# cpuConnectionBoard.net
KiCad netlist of a schematic drawn in EAGLE
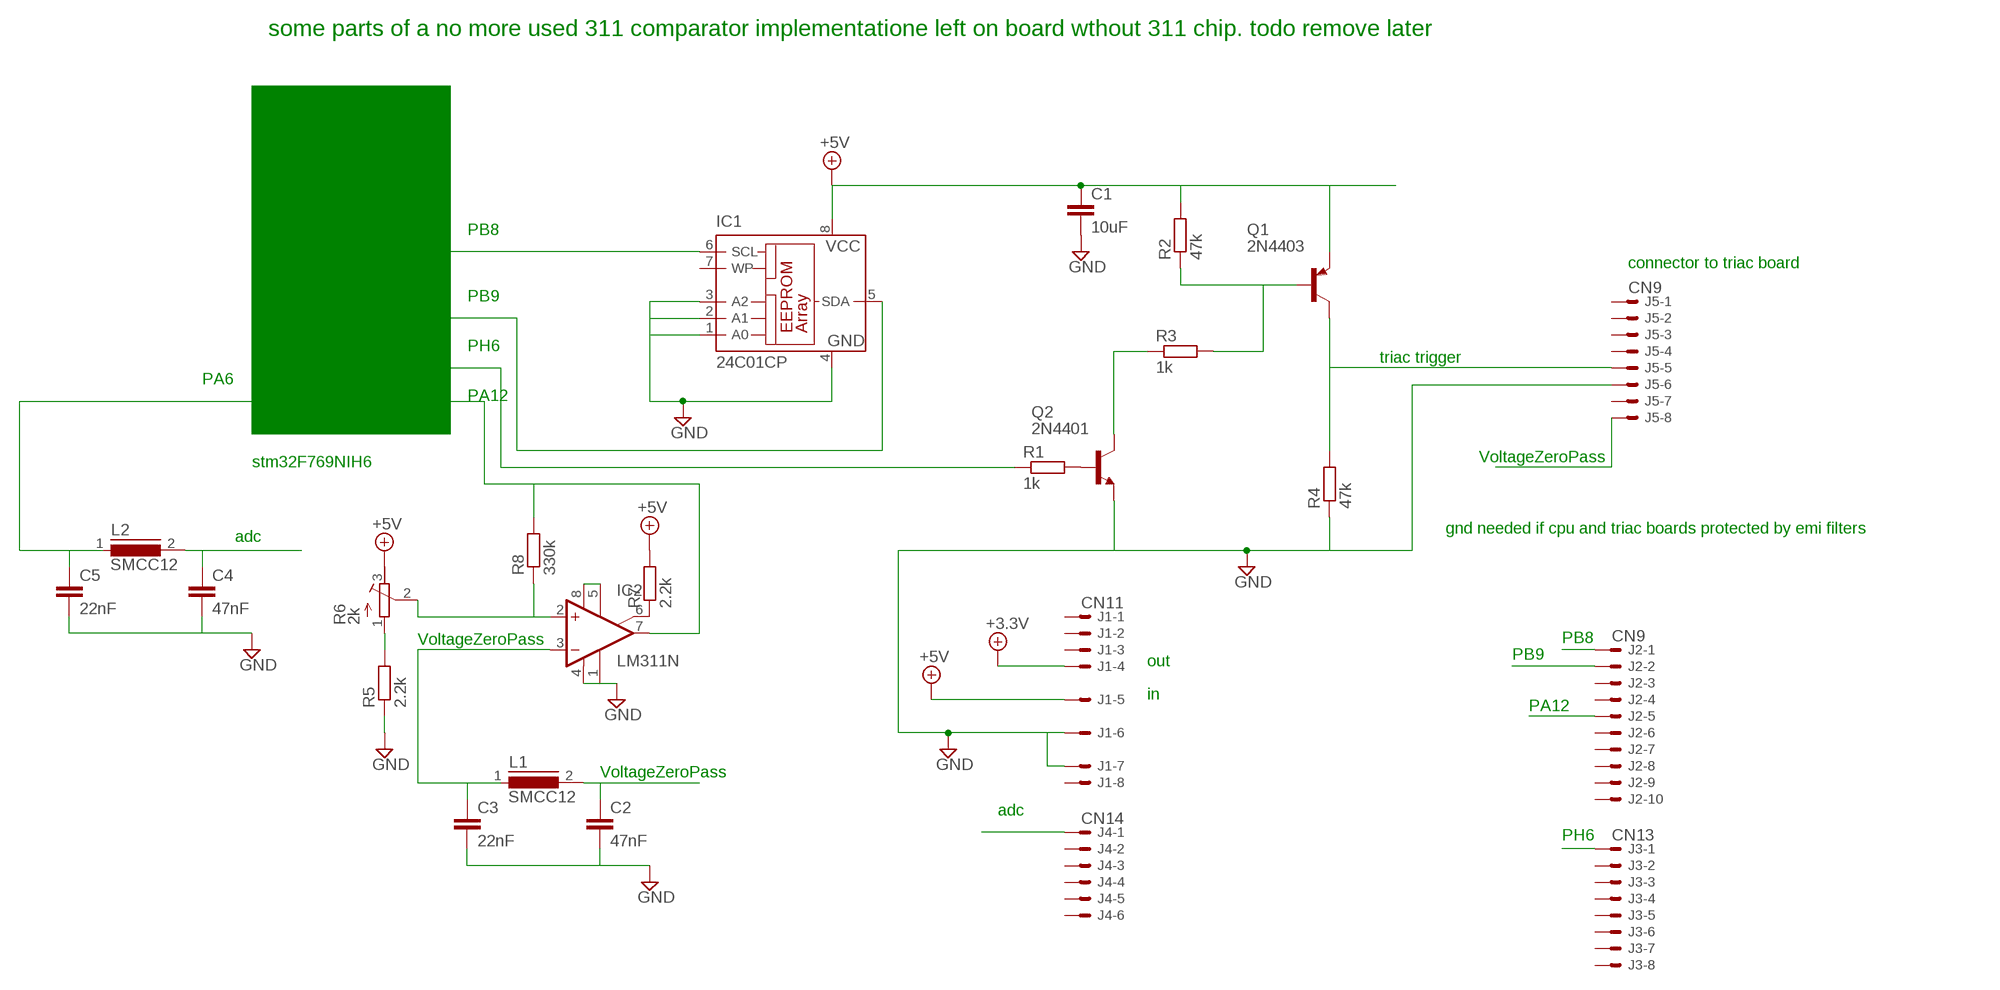
[diagram p0: schematic, sheet 1]

(export (version "E")
  (design (tool "Eeschema 10.0.6"))
  (components
    (comp (ref "C1")
      (value "10uF")
      (footprint "eagle-import:C050-030X075")
      (libsource (lib "eagle-import") (part "C-EU050-030X075"))
    )
    (comp (ref "C2")
      (value "47nF")
      (footprint "eagle-import:C050-030X075")
      (libsource (lib "eagle-import") (part "C-EU050-030X075"))
    )
    (comp (ref "C3")
      (value "22nF")
      (footprint "eagle-import:C050-030X075")
      (libsource (lib "eagle-import") (part "C-EU050-030X075"))
    )
    (comp (ref "C4")
      (value "47nF")
      (footprint "eagle-import:C050-030X075")
      (libsource (lib "eagle-import") (part "C-EU050-030X075"))
    )
    (comp (ref "C5")
      (value "22nF")
      (footprint "eagle-import:C050-030X075")
      (libsource (lib "eagle-import") (part "C-EU050-030X075"))
    )
    (comp (ref "IC1")
      (value "24C01CP")
      (footprint "eagle-import:DIL8")
      (fields (field (name "MF") "MICROCHIP") (field (name "MPN") "24C01C/P"))
      (libsource (lib "eagle-import") (part "24CP01C"))
    )
    (comp (ref "IC2")
      (value "LM311N")
      (footprint "eagle-import:DIL08")
      (libsource (lib "eagle-import") (part "LM311N"))
    )
    (comp (ref "J1")
      (value "CN11")
      (footprint "eagle-import:XF2E-0815-1")
      (fields (field (name "MPN") "XF2E-0815-1"))
      (libsource (lib "eagle-import") (part "XF2-08?15-1E"))
    )
    (comp (ref "J2")
      (value "CN9")
      (footprint "eagle-import:XF2E-1015-1")
      (fields (field (name "MPN") "XF2E-1015-1"))
      (libsource (lib "eagle-import") (part "XF2-10?15-1E"))
    )
    (comp (ref "J3")
      (value "CN13")
      (footprint "eagle-import:XF2E-0815-1")
      (fields (field (name "MPN") "XF2E-0815-1"))
      (libsource (lib "eagle-import") (part "XF2-08?15-1E"))
    )
    (comp (ref "J4")
      (value "CN14")
      (footprint "eagle-import:XF2E-0815-1")
      (fields (field (name "MPN") "XF2E-0815-1"))
      (libsource (lib "eagle-import") (part "XF2-08?15-1E"))
    )
    (comp (ref "J5")
      (value "CN9")
      (footprint "eagle-import:XF2E-1015-1")
      (fields (field (name "MPN") "XF2E-1015-1"))
      (libsource (lib "eagle-import") (part "XF2-10?15-1E"))
    )
    (comp (ref "L1")
      (value "SMCC12")
      (footprint "eagle-import:SMCC12")
      (libsource (lib "eagle-import") (part "SMCC12"))
    )
    (comp (ref "L2")
      (value "SMCC12")
      (footprint "eagle-import:SMCC12")
      (libsource (lib "eagle-import") (part "SMCC12"))
    )
    (comp (ref "Q1")
      (value "2N4403")
      (footprint "eagle-import:TO3")
      (libsource (lib "eagle-import") (part "2N4902"))
    )
    (comp (ref "Q2")
      (value "2N4401")
      (footprint "eagle-import:TO92")
      (libsource (lib "eagle-import") (part "2N4416"))
    )
    (comp (ref "R1")
      (value "1k")
      (footprint "eagle-import:0309_12")
      (libsource (lib "eagle-import") (part "R-EU_0309/12"))
    )
    (comp (ref "R2")
      (value "47k")
      (footprint "eagle-import:0309_12")
      (libsource (lib "eagle-import") (part "R-EU_0309/12"))
    )
    (comp (ref "R3")
      (value "1k")
      (footprint "eagle-import:0309_12")
      (libsource (lib "eagle-import") (part "R-EU_0309/12"))
    )
    (comp (ref "R4")
      (value "47k")
      (footprint "eagle-import:0309_12")
      (libsource (lib "eagle-import") (part "R-EU_0309/12"))
    )
    (comp (ref "R5")
      (value "2.2k")
      (footprint "eagle-import:0309_12")
      (libsource (lib "eagle-import") (part "R-EU_0309/12"))
    )
    (comp (ref "R6")
      (value "2k")
      (footprint "eagle-import:RTRIM64P")
      (libsource (lib "eagle-import") (part "R-TRIMM64P"))
    )
    (comp (ref "R7")
      (value "2.2k")
      (footprint "eagle-import:0309_12")
      (libsource (lib "eagle-import") (part "R-EU_0309/12"))
    )
    (comp (ref "R8")
      (value "330k")
      (footprint "eagle-import:0309_12")
      (libsource (lib "eagle-import") (part "R-EU_0309/12"))
    )
  )
  (nets
    (net (code "1") (name "+3.3V") (class "Default")
      (node (ref "C1") (pin "1") (pinfunction "1_1") (pintype "passive"))
      (node (ref "IC1") (pin "8") (pinfunction "VCC_8") (pintype "power_in"))
      (node (ref "J1") (pin "4") (pinfunction "MS_4") (pintype "passive"))
      (node (ref "J1") (pin "5") (pinfunction "MS_5") (pintype "passive"))
      (node (ref "Q1") (pin "E") (pinfunction "E_E") (pintype "passive"))
      (node (ref "R2") (pin "2") (pinfunction "2_2") (pintype "passive"))
      (node (ref "R6") (pin "3") (pinfunction "E_3") (pintype "passive"))
      (node (ref "R7") (pin "2") (pinfunction "2_2") (pintype "passive"))
    )
    (net (code "2") (name "GND") (class "Default")
      (node (ref "C1") (pin "2") (pinfunction "2_2") (pintype "passive"))
      (node (ref "C2") (pin "2") (pinfunction "2_2") (pintype "passive"))
      (node (ref "C3") (pin "2") (pinfunction "2_2") (pintype "passive"))
      (node (ref "C4") (pin "2") (pinfunction "2_2") (pintype "passive"))
      (node (ref "C5") (pin "2") (pinfunction "2_2") (pintype "passive"))
      (node (ref "IC1") (pin "1") (pinfunction "A0_1") (pintype "input"))
      (node (ref "IC1") (pin "2") (pinfunction "A1_2") (pintype "input"))
      (node (ref "IC1") (pin "3") (pinfunction "A2_3") (pintype "input"))
      (node (ref "IC1") (pin "4") (pinfunction "GND_4") (pintype "power_in"))
      (node (ref "IC2") (pin "4") (pinfunction "V-_4") (pintype "power_in"))
      (node (ref "J1") (pin "6") (pinfunction "MS_6") (pintype "passive"))
      (node (ref "J1") (pin "7") (pinfunction "MS_7") (pintype "passive"))
      (node (ref "J5") (pin "6") (pinfunction "MS_6") (pintype "passive"))
      (node (ref "Q2") (pin "3") (pinfunction "E_3") (pintype "passive"))
      (node (ref "R4") (pin "1") (pinfunction "1_1") (pintype "passive"))
      (node (ref "R5") (pin "1") (pinfunction "1_1") (pintype "passive"))
    )
    (net (code "3") (name "Net-(C2-Pad1)") (class "Default")
      (node (ref "C2") (pin "1") (pinfunction "1_1") (pintype "passive"))
      (node (ref "L1") (pin "2") (pinfunction "2_2") (pintype "passive"))
    )
    (net (code "4") (name "Net-(C4-Pad1)") (class "Default")
      (node (ref "C4") (pin "1") (pinfunction "1_1") (pintype "passive"))
      (node (ref "L2") (pin "2") (pinfunction "2_2") (pintype "passive"))
    )
    (net (code "5") (name "Net-(C5-Pad1)") (class "Default")
      (node (ref "C5") (pin "1") (pinfunction "1_1") (pintype "passive"))
      (node (ref "L2") (pin "1") (pinfunction "1_1") (pintype "passive"))
    )
    (net (code "6") (name "Net-(IC2-+IN)") (class "Default")
      (node (ref "IC2") (pin "2") (pinfunction "+IN_2") (pintype "input"))
      (node (ref "R6") (pin "2") (pinfunction "S_2") (pintype "passive"))
      (node (ref "R8") (pin "1") (pinfunction "1_1") (pintype "passive"))
    )
    (net (code "7") (name "Net-(IC2--IN)") (class "Default")
      (node (ref "C3") (pin "1") (pinfunction "1_1") (pintype "passive"))
      (node (ref "IC2") (pin "3") (pinfunction "-IN_3") (pintype "input"))
    )
    (net (code "8") (name "Net-(IC2-ON)") (class "Default")
      (node (ref "IC2") (pin "5") (pinfunction "ON_5") (pintype "passive"))
      (node (ref "IC2") (pin "8") (pinfunction "V+_8") (pintype "power_in"))
    )
    (net (code "9") (name "Net-(IC2-ON{slash}STR)") (class "Default")
      (node (ref "IC2") (pin "6") (pinfunction "ON/STR_6") (pintype "passive"))
      (node (ref "R7") (pin "1") (pinfunction "1_1") (pintype "passive"))
    )
    (net (code "10") (name "Net-(IC2-OUT)") (class "Default")
      (node (ref "IC2") (pin "7") (pinfunction "OUT_7") (pintype "output"))
      (node (ref "R8") (pin "2") (pinfunction "2_2") (pintype "passive"))
    )
    (net (code "11") (name "Net-(J5F-MS)") (class "Default")
      (node (ref "J5") (pin "5") (pinfunction "MS_5") (pintype "passive"))
      (node (ref "Q1") (pin "C") (pinfunction "C_C") (pintype "passive"))
      (node (ref "Q1") (pin "C/") (pinfunction "C_C/") (pintype "passive"))
      (node (ref "R4") (pin "2") (pinfunction "2_2") (pintype "passive"))
    )
    (net (code "12") (name "Net-(Q1-PadB)") (class "Default")
      (node (ref "Q1") (pin "B") (pinfunction "B_B") (pintype "passive"))
      (node (ref "R2") (pin "1") (pinfunction "1_1") (pintype "passive"))
      (node (ref "R3") (pin "2") (pinfunction "2_2") (pintype "passive"))
    )
    (net (code "13") (name "Net-(Q2-B)") (class "Default")
      (node (ref "Q2") (pin "2") (pinfunction "B_2") (pintype "passive"))
      (node (ref "R1") (pin "2") (pinfunction "2_2") (pintype "passive"))
    )
    (net (code "14") (name "Net-(Q2-C)") (class "Default")
      (node (ref "Q2") (pin "1") (pinfunction "C_1") (pintype "passive"))
      (node (ref "R3") (pin "1") (pinfunction "1_1") (pintype "passive"))
    )
    (net (code "15") (name "Net-(R6-A)") (class "Default")
      (node (ref "R5") (pin "2") (pinfunction "2_2") (pintype "passive"))
      (node (ref "R6") (pin "1") (pinfunction "A_1") (pintype "passive"))
    )
    (net (code "16") (name "unconnected-(IC1-SCL-Pad6)") (class "Default")
      (node (ref "IC1") (pin "6") (pinfunction "SCL_6") (pintype "input"))
    )
    (net (code "17") (name "unconnected-(IC1-SDA-Pad5)") (class "Default")
      (node (ref "IC1") (pin "5") (pinfunction "SDA_5") (pintype "bidirectional"))
    )
    (net (code "18") (name "unconnected-(IC1-WP-Pad7)") (class "Default")
      (node (ref "IC1") (pin "7") (pinfunction "WP_7") (pintype "input"))
    )
    (net (code "19") (name "unconnected-(IC2-GND-Pad1)") (class "Default")
      (node (ref "IC2") (pin "1") (pinfunction "GND_1") (pintype "passive"))
    )
    (net (code "20") (name "unconnected-(J1A-MSV-Pad1)") (class "Default")
      (node (ref "J1") (pin "1") (pinfunction "MSV_1") (pintype "passive"))
    )
    (net (code "21") (name "unconnected-(J1B-MS-Pad2)") (class "Default")
      (node (ref "J1") (pin "2") (pinfunction "MS_2") (pintype "passive"))
    )
    (net (code "22") (name "unconnected-(J1C-MS-Pad3)") (class "Default")
      (node (ref "J1") (pin "3") (pinfunction "MS_3") (pintype "passive"))
    )
    (net (code "23") (name "unconnected-(J1H-MS-Pad8)") (class "Default")
      (node (ref "J1") (pin "8") (pinfunction "MS_8") (pintype "passive"))
    )
    (net (code "24") (name "unconnected-(J2A-MSV-Pad1)") (class "Default")
      (node (ref "J2") (pin "1") (pinfunction "MSV_1") (pintype "passive"))
    )
    (net (code "25") (name "unconnected-(J2B-MS-Pad10)") (class "Default")
      (node (ref "J2") (pin "10") (pinfunction "MS_10") (pintype "passive"))
    )
    (net (code "26") (name "unconnected-(J2C-MS-Pad2)") (class "Default")
      (node (ref "J2") (pin "2") (pinfunction "MS_2") (pintype "passive"))
    )
    (net (code "27") (name "unconnected-(J2D-MS-Pad3)") (class "Default")
      (node (ref "J2") (pin "3") (pinfunction "MS_3") (pintype "passive"))
    )
    (net (code "28") (name "unconnected-(J2E-MS-Pad4)") (class "Default")
      (node (ref "J2") (pin "4") (pinfunction "MS_4") (pintype "passive"))
    )
    (net (code "29") (name "unconnected-(J2F-MS-Pad5)") (class "Default")
      (node (ref "J2") (pin "5") (pinfunction "MS_5") (pintype "passive"))
    )
    (net (code "30") (name "unconnected-(J2G-MS-Pad6)") (class "Default")
      (node (ref "J2") (pin "6") (pinfunction "MS_6") (pintype "passive"))
    )
    (net (code "31") (name "unconnected-(J2H-MS-Pad7)") (class "Default")
      (node (ref "J2") (pin "7") (pinfunction "MS_7") (pintype "passive"))
    )
    (net (code "32") (name "unconnected-(J2I-MS-Pad8)") (class "Default")
      (node (ref "J2") (pin "8") (pinfunction "MS_8") (pintype "passive"))
    )
    (net (code "33") (name "unconnected-(J2J-MS-Pad9)") (class "Default")
      (node (ref "J2") (pin "9") (pinfunction "MS_9") (pintype "passive"))
    )
    (net (code "34") (name "unconnected-(J3A-MSV-Pad1)") (class "Default")
      (node (ref "J3") (pin "1") (pinfunction "MSV_1") (pintype "passive"))
    )
    (net (code "35") (name "unconnected-(J3B-MS-Pad2)") (class "Default")
      (node (ref "J3") (pin "2") (pinfunction "MS_2") (pintype "passive"))
    )
    (net (code "36") (name "unconnected-(J3C-MS-Pad3)") (class "Default")
      (node (ref "J3") (pin "3") (pinfunction "MS_3") (pintype "passive"))
    )
    (net (code "37") (name "unconnected-(J3D-MS-Pad4)") (class "Default")
      (node (ref "J3") (pin "4") (pinfunction "MS_4") (pintype "passive"))
    )
    (net (code "38") (name "unconnected-(J3E-MS-Pad5)") (class "Default")
      (node (ref "J3") (pin "5") (pinfunction "MS_5") (pintype "passive"))
    )
    (net (code "39") (name "unconnected-(J3F-MS-Pad6)") (class "Default")
      (node (ref "J3") (pin "6") (pinfunction "MS_6") (pintype "passive"))
    )
    (net (code "40") (name "unconnected-(J3G-MS-Pad7)") (class "Default")
      (node (ref "J3") (pin "7") (pinfunction "MS_7") (pintype "passive"))
    )
    (net (code "41") (name "unconnected-(J3H-MS-Pad8)") (class "Default")
      (node (ref "J3") (pin "8") (pinfunction "MS_8") (pintype "passive"))
    )
    (net (code "42") (name "unconnected-(J4A-MSV-Pad1)") (class "Default")
      (node (ref "J4") (pin "1") (pinfunction "MSV_1") (pintype "passive"))
    )
    (net (code "43") (name "unconnected-(J4B-MS-Pad2)") (class "Default")
      (node (ref "J4") (pin "2") (pinfunction "MS_2") (pintype "passive"))
    )
    (net (code "44") (name "unconnected-(J4C-MS-Pad3)") (class "Default")
      (node (ref "J4") (pin "3") (pinfunction "MS_3") (pintype "passive"))
    )
    (net (code "45") (name "unconnected-(J4D-MS-Pad4)") (class "Default")
      (node (ref "J4") (pin "4") (pinfunction "MS_4") (pintype "passive"))
    )
    (net (code "46") (name "unconnected-(J4E-MS-Pad5)") (class "Default")
      (node (ref "J4") (pin "5") (pinfunction "MS_5") (pintype "passive"))
    )
    (net (code "47") (name "unconnected-(J4F-MS-Pad6)") (class "Default")
      (node (ref "J4") (pin "6") (pinfunction "MS_6") (pintype "passive"))
    )
    (net (code "48") (name "unconnected-(J5A-MSV-Pad1)") (class "Default")
      (node (ref "J5") (pin "1") (pinfunction "MSV_1") (pintype "passive"))
    )
    (net (code "49") (name "unconnected-(J5C-MS-Pad2)") (class "Default")
      (node (ref "J5") (pin "2") (pinfunction "MS_2") (pintype "passive"))
    )
    (net (code "50") (name "unconnected-(J5D-MS-Pad3)") (class "Default")
      (node (ref "J5") (pin "3") (pinfunction "MS_3") (pintype "passive"))
    )
    (net (code "51") (name "unconnected-(J5E-MS-Pad4)") (class "Default")
      (node (ref "J5") (pin "4") (pinfunction "MS_4") (pintype "passive"))
    )
    (net (code "52") (name "unconnected-(J5H-MS-Pad7)") (class "Default")
      (node (ref "J5") (pin "7") (pinfunction "MS_7") (pintype "passive"))
    )
    (net (code "53") (name "unconnected-(J5I-MS-Pad8)") (class "Default")
      (node (ref "J5") (pin "8") (pinfunction "MS_8") (pintype "passive"))
    )
    (net (code "54") (name "unconnected-(L1-Pad1)") (class "Default")
      (node (ref "L1") (pin "1") (pinfunction "1_1") (pintype "passive"))
    )
    (net (code "55") (name "unconnected-(R1-Pad1)") (class "Default")
      (node (ref "R1") (pin "1") (pinfunction "1_1") (pintype "passive"))
    )
  )
)
